# PCB.net
KiCad netlist of a schematic drawn in Altium Designer
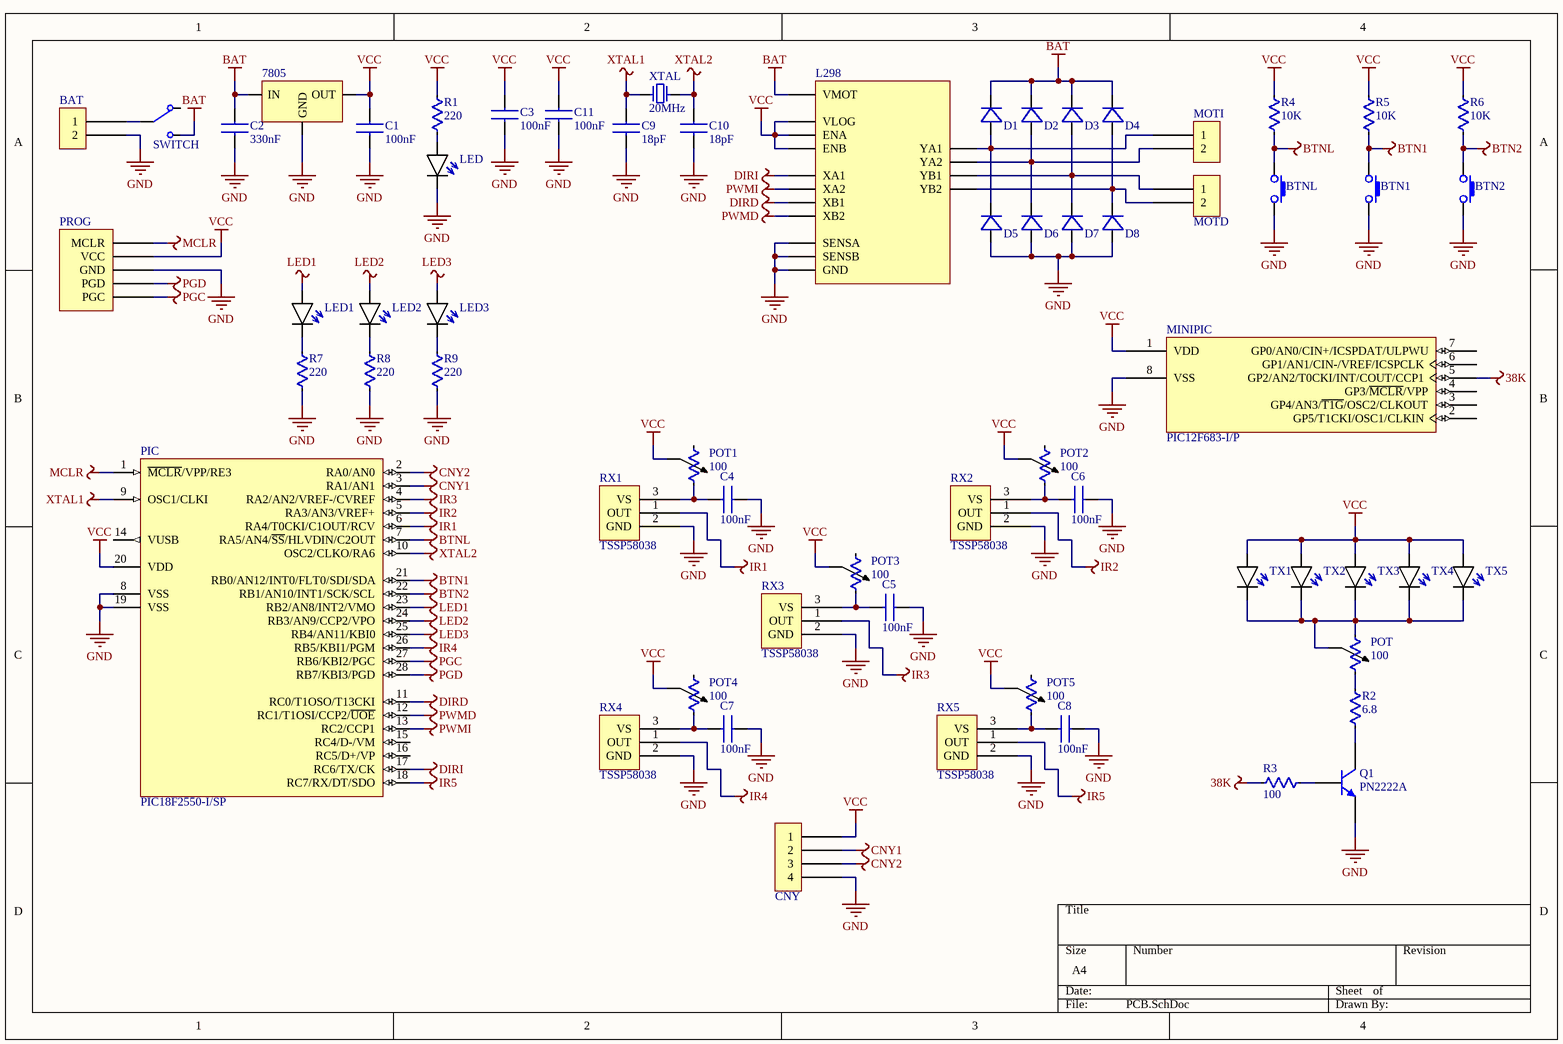
[diagram p0: PCB.SchDoc]

(export (version "E")
  (design (tool "Eeschema 10.0.6"))
  (components
    (comp (ref "7805")
      (value "LM78XX")
      (footprint "TO-220-FLAT")
      (libsource (lib "AltiumLibrary") (part "LM78XX"))
    )
    (comp (ref "BAT")
      (value "Header 1x2")
      (footprint "HEADER 1x2")
      (libsource (lib "AltiumLibrary") (part "Header 1x2"))
    )
    (comp (ref "BTN1")
      (value "BUTTON_SMALL_4PIN")
      (footprint "TACT_SWITCH-SMALL-4PIN")
      (libsource (lib "AltiumLibrary") (part "BUTTON_SMALL_4PIN"))
    )
    (comp (ref "BTN2")
      (value "BUTTON_SMALL_4PIN")
      (footprint "TACT_SWITCH-SMALL-4PIN")
      (libsource (lib "AltiumLibrary") (part "BUTTON_SMALL_4PIN"))
    )
    (comp (ref "BTNL")
      (value "BUTTON_SMALL_4PIN")
      (footprint "TACT_SWITCH-SMALL-4PIN")
      (libsource (lib "AltiumLibrary") (part "BUTTON_SMALL_4PIN"))
    )
    (comp (ref "C1")
      (value "100nF")
      (footprint "CAP-CER")
      (fields (field (name "Comment") "CAP-CER"))
      (libsource (lib "AltiumLibrary") (part "CAP-CER"))
    )
    (comp (ref "C2")
      (value "330nF")
      (footprint "CAP-CER")
      (fields (field (name "Comment") "CAP-CER"))
      (libsource (lib "AltiumLibrary") (part "CAP-CER"))
    )
    (comp (ref "C3")
      (value "100nF")
      (footprint "CAP-CER")
      (fields (field (name "Comment") "CAP-CER"))
      (libsource (lib "AltiumLibrary") (part "CAP-CER"))
    )
    (comp (ref "C4")
      (value "100nF")
      (footprint "CAP-CER")
      (fields (field (name "Comment") "CAP-CER"))
      (libsource (lib "AltiumLibrary") (part "CAP-CER"))
    )
    (comp (ref "C5")
      (value "100nF")
      (footprint "CAP-CER")
      (fields (field (name "Comment") "CAP-CER"))
      (libsource (lib "AltiumLibrary") (part "CAP-CER"))
    )
    (comp (ref "C6")
      (value "100nF")
      (footprint "CAP-CER")
      (fields (field (name "Comment") "CAP-CER"))
      (libsource (lib "AltiumLibrary") (part "CAP-CER"))
    )
    (comp (ref "C7")
      (value "100nF")
      (footprint "CAP-CER")
      (fields (field (name "Comment") "CAP-CER"))
      (libsource (lib "AltiumLibrary") (part "CAP-CER"))
    )
    (comp (ref "C8")
      (value "100nF")
      (footprint "CAP-CER")
      (fields (field (name "Comment") "CAP-CER"))
      (libsource (lib "AltiumLibrary") (part "CAP-CER"))
    )
    (comp (ref "C9")
      (value "18pF")
      (footprint "CAP-CER")
      (fields (field (name "Comment") "CAP-CER"))
      (libsource (lib "AltiumLibrary") (part "CAP-CER"))
    )
    (comp (ref "C10")
      (value "18pF")
      (footprint "CAP-CER")
      (fields (field (name "Comment") "CAP-CER"))
      (libsource (lib "AltiumLibrary") (part "CAP-CER"))
    )
    (comp (ref "C11")
      (value "100nF")
      (footprint "CAP-CER")
      (fields (field (name "Comment") "CAP-CER"))
      (libsource (lib "AltiumLibrary") (part "CAP-CER"))
    )
    (comp (ref "CNY")
      (value "Header 1x4")
      (footprint "Header 1x4")
      (libsource (lib "AltiumLibrary") (part "Header 1x4"))
    )
    (comp (ref "D1")
      (value "DIODE")
      (footprint "DO-41 RADIAL")
      (libsource (lib "AltiumLibrary") (part "DIODE"))
    )
    (comp (ref "D2")
      (value "DIODE")
      (footprint "DO-41 RADIAL")
      (libsource (lib "AltiumLibrary") (part "DIODE"))
    )
    (comp (ref "D3")
      (value "DIODE")
      (footprint "DO-41 RADIAL")
      (libsource (lib "AltiumLibrary") (part "DIODE"))
    )
    (comp (ref "D4")
      (value "DIODE")
      (footprint "DO-41 RADIAL")
      (libsource (lib "AltiumLibrary") (part "DIODE"))
    )
    (comp (ref "D5")
      (value "DIODE")
      (footprint "DO-41 RADIAL")
      (libsource (lib "AltiumLibrary") (part "DIODE"))
    )
    (comp (ref "D6")
      (value "DIODE")
      (footprint "DO-41 RADIAL")
      (libsource (lib "AltiumLibrary") (part "DIODE"))
    )
    (comp (ref "D7")
      (value "DIODE")
      (footprint "DO-41 RADIAL")
      (libsource (lib "AltiumLibrary") (part "DIODE"))
    )
    (comp (ref "D8")
      (value "DIODE")
      (footprint "DO-41 RADIAL")
      (libsource (lib "AltiumLibrary") (part "DIODE"))
    )
    (comp (ref "L298")
      (value "L298")
      (footprint "Multiwatt15")
      (libsource (lib "AltiumLibrary") (part "L298"))
    )
    (comp (ref "LED") (value "LED") (footprint "LED-3MM-RED") (libsource (lib "AltiumLibrary") (part "LED")))
    (comp (ref "LED1") (value "LED") (footprint "LED-3MM-RED") (libsource (lib "AltiumLibrary") (part "LED")))
    (comp (ref "LED2")
      (value "LED")
      (footprint "LED-3MM-YELLOW")
      (libsource (lib "AltiumLibrary") (part "LED"))
    )
    (comp (ref "LED3")
      (value "LED")
      (footprint "LED-3MM-GREEN")
      (libsource (lib "AltiumLibrary") (part "LED"))
    )
    (comp (ref "MINIPIC")
      (value "PIC12F683-I/P")
      (footprint "PDIP300-P8")
      (fields (field (name "PUBLISHER") "Altium Limited"))
      (libsource (lib "Microchip Microcontroller 8-Bit PIC12") (part "PIC12F683-I/P"))
    )
    (comp (ref "MOTD") (value "~") (footprint "HEADER 1x2") (libsource (lib "") (part "Header 1x2_1")))
    (comp (ref "MOTI") (value "~") (footprint "HEADER 1x2") (libsource (lib "") (part "Header 1x2_1")))
    (comp (ref "PIC")
      (value "PIC18F2550-I/SP")
      (footprint "SPDIP300-SP28")
      (fields (field (name "PUBLISHER") "Altium Limited"))
      (libsource (lib "Microchip Microcontroller 8-Bit PIC18") (part "PIC18F2550-I/SP"))
    )
    (comp (ref "POT")
      (value "100")
      (footprint "POT-10TURN")
      (fields (field (name "Comment") "POT"))
      (libsource (lib "AltiumLibrary") (part "POT"))
    )
    (comp (ref "POT1")
      (value "100")
      (footprint "POT-10TURN")
      (fields (field (name "Comment") "POT"))
      (libsource (lib "AltiumLibrary") (part "POT"))
    )
    (comp (ref "POT2")
      (value "100")
      (footprint "POT-10TURN")
      (fields (field (name "Comment") "POT"))
      (libsource (lib "AltiumLibrary") (part "POT"))
    )
    (comp (ref "POT3")
      (value "100")
      (footprint "POT-10TURN")
      (fields (field (name "Comment") "POT"))
      (libsource (lib "AltiumLibrary") (part "POT"))
    )
    (comp (ref "POT4")
      (value "100")
      (footprint "POT-10TURN")
      (fields (field (name "Comment") "POT"))
      (libsource (lib "AltiumLibrary") (part "POT"))
    )
    (comp (ref "POT5")
      (value "100")
      (footprint "POT-10TURN")
      (fields (field (name "Comment") "POT"))
      (libsource (lib "AltiumLibrary") (part "POT"))
    )
    (comp (ref "PROG")
      (value "~")
      (footprint "Header 1x5")
      (libsource (lib "AltiumLibrary") (part "Header Programmer"))
    )
    (comp (ref "Q1") (value "PN2222A") (footprint "TO-92") (libsource (lib "AltiumLibrary") (part "NPN")))
    (comp (ref "R1")
      (value "220")
      (footprint "RES-Axial-400mil")
      (fields (field (name "Comment") "RES"))
      (libsource (lib "") (part "RES_1"))
    )
    (comp (ref "R2")
      (value "6.8")
      (footprint "RES-Axial-400mil")
      (fields (field (name "Comment") "RES"))
      (libsource (lib "AltiumLibrary") (part "RES"))
    )
    (comp (ref "R3")
      (value "100")
      (footprint "RES-Axial-400mil")
      (fields (field (name "Comment") "RES"))
      (libsource (lib "") (part "RES_2"))
    )
    (comp (ref "R4")
      (value "10K")
      (footprint "RES-Axial-400mil")
      (fields (field (name "Comment") "RES"))
      (libsource (lib "") (part "RES_1"))
    )
    (comp (ref "R5")
      (value "10K")
      (footprint "RES-Axial-400mil")
      (fields (field (name "Comment") "RES"))
      (libsource (lib "") (part "RES_1"))
    )
    (comp (ref "R6")
      (value "10K")
      (footprint "RES-Axial-400mil")
      (fields (field (name "Comment") "RES"))
      (libsource (lib "") (part "RES_1"))
    )
    (comp (ref "R7")
      (value "220")
      (footprint "RES-RADIAL")
      (fields (field (name "Comment") "RES"))
      (libsource (lib "AltiumLibrary") (part "RES"))
    )
    (comp (ref "R8")
      (value "220")
      (footprint "RES-RADIAL")
      (fields (field (name "Comment") "RES"))
      (libsource (lib "AltiumLibrary") (part "RES"))
    )
    (comp (ref "R9")
      (value "220")
      (footprint "RES-RADIAL")
      (fields (field (name "Comment") "RES"))
      (libsource (lib "AltiumLibrary") (part "RES"))
    )
    (comp (ref "RX1")
      (value "TSSP58038")
      (footprint "TSSP58038")
      (libsource (lib "GlecerLib") (part "TSSP58038"))
    )
    (comp (ref "RX2")
      (value "TSSP58038")
      (footprint "TSSP58038")
      (libsource (lib "GlecerLib") (part "TSSP58038"))
    )
    (comp (ref "RX3")
      (value "TSSP58038")
      (footprint "TSSP58038")
      (libsource (lib "GlecerLib") (part "TSSP58038"))
    )
    (comp (ref "RX4")
      (value "TSSP58038")
      (footprint "TSSP58038")
      (libsource (lib "GlecerLib") (part "TSSP58038"))
    )
    (comp (ref "RX5")
      (value "TSSP58038")
      (footprint "TSSP58038")
      (libsource (lib "GlecerLib") (part "TSSP58038"))
    )
    (comp (ref "SWITCH")
      (value "SLIDE-SWITCH")
      (footprint "SWITCH")
      (libsource (lib "AltiumLibrary") (part "SLIDE-SWITCH"))
    )
    (comp (ref "TX1")
      (value "LED")
      (footprint "LED-3MM-YELLOW")
      (libsource (lib "AltiumLibrary") (part "LED"))
    )
    (comp (ref "TX2")
      (value "LED")
      (footprint "LED-3MM-YELLOW")
      (libsource (lib "AltiumLibrary") (part "LED"))
    )
    (comp (ref "TX3")
      (value "LED")
      (footprint "LED-3MM-YELLOW")
      (libsource (lib "AltiumLibrary") (part "LED"))
    )
    (comp (ref "TX4")
      (value "LED")
      (footprint "LED-3MM-YELLOW")
      (libsource (lib "AltiumLibrary") (part "LED"))
    )
    (comp (ref "TX5")
      (value "LED")
      (footprint "LED-3MM-YELLOW")
      (libsource (lib "AltiumLibrary") (part "LED"))
    )
    (comp (ref "XTAL")
      (value "XTAL")
      (footprint "CRYSTAL-TH")
      (fields (field (name "FREQUENCY") "20MHz"))
      (libsource (lib "AltiumLibrary") (part "XTAL"))
    )
  )
  (nets
    (net (code "1") (name "38K") (class "Default")
      (node (ref "MINIPIC") (pin "5") (pinfunction "GP2/AN2/T0CKI/INT/COUT/CCP1_5") (pintype "bidirectional"))
      (node (ref "R3") (pin "1") (pintype "passive"))
    )
    (net (code "2") (name "BAT") (class "Default")
      (node (ref "7805") (pin "1") (pinfunction "IN_1") (pintype "power_in"))
      (node (ref "C2") (pin "1") (pintype "passive"))
      (node (ref "D1") (pin "K") (pintype "passive"))
      (node (ref "D2") (pin "K") (pintype "passive"))
      (node (ref "D3") (pin "K") (pintype "passive"))
      (node (ref "D4") (pin "K") (pintype "passive"))
      (node (ref "L298") (pin "4") (pinfunction "VMOT_4") (pintype "passive"))
      (node (ref "SWITCH") (pin "3") (pintype "power_in"))
    )
    (net (code "3") (name "BTN1") (class "Default")
      (node (ref "BTN1") (pin "1") (pintype "passive"))
      (node (ref "PIC") (pin "21") (pinfunction "RB0/AN12/INT0/FLT0/SDI/SDA_21") (pintype "bidirectional"))
      (node (ref "R5") (pin "1") (pintype "passive"))
    )
    (net (code "4") (name "BTN2") (class "Default")
      (node (ref "BTN2") (pin "1") (pintype "passive"))
      (node (ref "PIC") (pin "22") (pinfunction "RB1/AN10/INT1/SCK/SCL_22") (pintype "bidirectional"))
      (node (ref "R6") (pin "1") (pintype "passive"))
    )
    (net (code "5") (name "BTNL") (class "Default")
      (node (ref "BTNL") (pin "1") (pintype "passive"))
      (node (ref "PIC") (pin "7") (pinfunction "RA5/AN4/~{SS}/HLVDIN/C2OUT_7") (pintype "bidirectional"))
      (node (ref "R4") (pin "1") (pintype "passive"))
    )
    (net (code "6") (name "CNY1") (class "Default")
      (node (ref "CNY") (pin "2") (pinfunction "2_2") (pintype "passive"))
      (node (ref "PIC") (pin "3") (pinfunction "RA1/AN1_3") (pintype "bidirectional"))
    )
    (net (code "7") (name "CNY2") (class "Default")
      (node (ref "CNY") (pin "3") (pinfunction "3_3") (pintype "passive"))
      (node (ref "PIC") (pin "2") (pinfunction "RA0/AN0_2") (pintype "bidirectional"))
    )
    (net (code "8") (name "DIRD") (class "Default")
      (node (ref "L298") (pin "12") (pinfunction "XB1_12") (pintype "passive"))
      (node (ref "PIC") (pin "11") (pinfunction "RC0/T1OSO/T13CKI_11") (pintype "bidirectional"))
    )
    (net (code "9") (name "DIRI") (class "Default")
      (node (ref "L298") (pin "5") (pinfunction "XA1_5") (pintype "passive"))
      (node (ref "PIC") (pin "17") (pinfunction "RC6/TX/CK_17") (pintype "bidirectional"))
    )
    (net (code "10") (name "GND") (class "Default")
      (node (ref "7805") (pin "2") (pinfunction "GND_2") (pintype "power_in"))
      (node (ref "BAT") (pin "2") (pinfunction "2_2") (pintype "passive"))
      (node (ref "BTN1") (pin "2") (pintype "passive"))
      (node (ref "BTN2") (pin "2") (pintype "passive"))
      (node (ref "BTNL") (pin "2") (pintype "passive"))
      (node (ref "C1") (pin "2") (pintype "passive"))
      (node (ref "C10") (pin "1") (pintype "passive"))
      (node (ref "C11") (pin "1") (pintype "passive"))
      (node (ref "C2") (pin "2") (pintype "passive"))
      (node (ref "C3") (pin "1") (pintype "passive"))
      (node (ref "C4") (pin "2") (pintype "passive"))
      (node (ref "C5") (pin "2") (pintype "passive"))
      (node (ref "C6") (pin "2") (pintype "passive"))
      (node (ref "C7") (pin "2") (pintype "passive"))
      (node (ref "C8") (pin "2") (pintype "passive"))
      (node (ref "C9") (pin "1") (pintype "passive"))
      (node (ref "CNY") (pin "4") (pinfunction "4_4") (pintype "passive"))
      (node (ref "D5") (pin "A") (pintype "passive"))
      (node (ref "D6") (pin "A") (pintype "passive"))
      (node (ref "D7") (pin "A") (pintype "passive"))
      (node (ref "D8") (pin "A") (pintype "passive"))
      (node (ref "L298") (pin "1") (pinfunction "SENSA_1") (pintype "passive"))
      (node (ref "L298") (pin "15") (pinfunction "SENSB_15") (pintype "passive"))
      (node (ref "L298") (pin "8") (pinfunction "GND_8") (pintype "passive"))
      (node (ref "LED") (pin "K") (pintype "passive"))
      (node (ref "MINIPIC") (pin "8") (pinfunction "VSS_8") (pintype "power_in"))
      (node (ref "PIC") (pin "19") (pinfunction "VSS_19") (pintype "power_in"))
      (node (ref "PIC") (pin "8") (pinfunction "VSS_8") (pintype "power_in"))
      (node (ref "PROG") (pin "3") (pinfunction "GND_3") (pintype "power_in"))
      (node (ref "Q1") (pin "E") (pinfunction "E_E") (pintype "passive"))
      (node (ref "R7") (pin "2") (pintype "passive"))
      (node (ref "R8") (pin "2") (pintype "passive"))
      (node (ref "R9") (pin "2") (pintype "passive"))
      (node (ref "RX1") (pin "2") (pinfunction "GND_2") (pintype "power_in"))
      (node (ref "RX2") (pin "2") (pinfunction "GND_2") (pintype "power_in"))
      (node (ref "RX3") (pin "2") (pinfunction "GND_2") (pintype "power_in"))
      (node (ref "RX4") (pin "2") (pinfunction "GND_2") (pintype "power_in"))
      (node (ref "RX5") (pin "2") (pinfunction "GND_2") (pintype "power_in"))
    )
    (net (code "11") (name "IR1") (class "Default")
      (node (ref "PIC") (pin "6") (pinfunction "RA4/T0CKI/C1OUT/RCV_6") (pintype "bidirectional"))
      (node (ref "RX1") (pin "1") (pinfunction "OUT_1") (pintype "power_in"))
    )
    (net (code "12") (name "IR2") (class "Default")
      (node (ref "PIC") (pin "5") (pinfunction "RA3/AN3/VREF+_5") (pintype "bidirectional"))
      (node (ref "RX2") (pin "1") (pinfunction "OUT_1") (pintype "power_in"))
    )
    (net (code "13") (name "IR3") (class "Default")
      (node (ref "PIC") (pin "4") (pinfunction "RA2/AN2/VREF-/CVREF_4") (pintype "bidirectional"))
      (node (ref "RX3") (pin "1") (pinfunction "OUT_1") (pintype "power_in"))
    )
    (net (code "14") (name "IR4") (class "Default")
      (node (ref "PIC") (pin "26") (pinfunction "RB5/KBI1/PGM_26") (pintype "bidirectional"))
      (node (ref "RX4") (pin "1") (pinfunction "OUT_1") (pintype "power_in"))
    )
    (net (code "15") (name "IR5") (class "Default")
      (node (ref "PIC") (pin "18") (pinfunction "RC7/RX/DT/SDO_18") (pintype "bidirectional"))
      (node (ref "RX5") (pin "1") (pinfunction "OUT_1") (pintype "power_in"))
    )
    (net (code "16") (name "LED1") (class "Default")
      (node (ref "LED1") (pin "A") (pintype "passive"))
      (node (ref "PIC") (pin "23") (pinfunction "RB2/AN8/INT2/VMO_23") (pintype "bidirectional"))
    )
    (net (code "17") (name "LED2") (class "Default")
      (node (ref "LED2") (pin "A") (pintype "passive"))
      (node (ref "PIC") (pin "24") (pinfunction "RB3/AN9/CCP2/VPO_24") (pintype "bidirectional"))
    )
    (net (code "18") (name "LED3") (class "Default")
      (node (ref "LED3") (pin "A") (pintype "passive"))
      (node (ref "PIC") (pin "25") (pinfunction "RB4/AN11/KBI0_25") (pintype "bidirectional"))
    )
    (net (code "19") (name "MCLR") (class "Default")
      (node (ref "PIC") (pin "1") (pinfunction "~{MCLR}/VPP/RE3_1") (pintype "input"))
      (node (ref "PROG") (pin "1") (pinfunction "MCLR_1") (pintype "passive"))
    )
    (net (code "20") (name "Net-(BAT-Pad1)") (class "Default")
      (node (ref "BAT") (pin "1") (pinfunction "1_1") (pintype "passive"))
      (node (ref "SWITCH") (pin "2") (pintype "power_in"))
    )
    (net (code "21") (name "Net-(L298-YA1)") (class "Default")
      (node (ref "D1") (pin "A") (pintype "passive"))
      (node (ref "D5") (pin "K") (pintype "passive"))
      (node (ref "L298") (pin "2") (pinfunction "YA1_2") (pintype "passive"))
      (node (ref "MOTI") (pin "1") (pinfunction "1_1") (pintype "passive"))
    )
    (net (code "22") (name "Net-(L298-YA2)") (class "Default")
      (node (ref "D2") (pin "A") (pintype "passive"))
      (node (ref "D6") (pin "K") (pintype "passive"))
      (node (ref "L298") (pin "3") (pinfunction "YA2_3") (pintype "passive"))
      (node (ref "MOTI") (pin "2") (pinfunction "2_2") (pintype "passive"))
    )
    (net (code "23") (name "Net-(L298-YB1)") (class "Default")
      (node (ref "D3") (pin "A") (pintype "passive"))
      (node (ref "D7") (pin "K") (pintype "passive"))
      (node (ref "L298") (pin "13") (pinfunction "YB1_13") (pintype "passive"))
      (node (ref "MOTD") (pin "1") (pinfunction "1_1") (pintype "passive"))
    )
    (net (code "24") (name "Net-(L298-YB2)") (class "Default")
      (node (ref "D4") (pin "A") (pintype "passive"))
      (node (ref "D8") (pin "K") (pintype "passive"))
      (node (ref "L298") (pin "14") (pinfunction "YB2_14") (pintype "passive"))
      (node (ref "MOTD") (pin "2") (pinfunction "2_2") (pintype "passive"))
    )
    (net (code "25") (name "Net-(LED-PadA)") (class "Default")
      (node (ref "LED") (pin "A") (pintype "passive"))
      (node (ref "R1") (pin "1") (pintype "passive"))
    )
    (net (code "26") (name "Net-(LED1-PadK)") (class "Default")
      (node (ref "LED1") (pin "K") (pintype "passive"))
      (node (ref "R7") (pin "1") (pintype "passive"))
    )
    (net (code "27") (name "Net-(LED2-PadK)") (class "Default")
      (node (ref "LED2") (pin "K") (pintype "passive"))
      (node (ref "R8") (pin "1") (pintype "passive"))
    )
    (net (code "28") (name "Net-(LED3-PadK)") (class "Default")
      (node (ref "LED3") (pin "K") (pintype "passive"))
      (node (ref "R9") (pin "1") (pintype "passive"))
    )
    (net (code "29") (name "Net-(POT-Pad1)") (class "Default")
      (node (ref "POT") (pin "1") (pintype "passive"))
      (node (ref "R2") (pin "1") (pintype "passive"))
    )
    (net (code "30") (name "Net-(POT-Pad2)") (class "Default")
      (node (ref "POT") (pin "2") (pintype "passive"))
      (node (ref "POT") (pin "3") (pintype "passive"))
      (node (ref "TX1") (pin "K") (pintype "passive"))
      (node (ref "TX2") (pin "K") (pintype "passive"))
      (node (ref "TX3") (pin "K") (pintype "passive"))
      (node (ref "TX4") (pin "K") (pintype "passive"))
      (node (ref "TX5") (pin "K") (pintype "passive"))
    )
    (net (code "31") (name "Net-(Q1-PadB)") (class "Default")
      (node (ref "Q1") (pin "B") (pinfunction "B_B") (pintype "passive"))
      (node (ref "R3") (pin "2") (pintype "passive"))
    )
    (net (code "32") (name "Net-(Q1-PadC)") (class "Default")
      (node (ref "Q1") (pin "C") (pinfunction "C_C") (pintype "passive"))
      (node (ref "R2") (pin "2") (pintype "passive"))
    )
    (net (code "33") (name "Net-(RX1-VS)") (class "Default")
      (node (ref "C4") (pin "1") (pintype "passive"))
      (node (ref "POT1") (pin "1") (pintype "passive"))
      (node (ref "RX1") (pin "3") (pinfunction "VS_3") (pintype "power_in"))
    )
    (net (code "34") (name "Net-(RX2-VS)") (class "Default")
      (node (ref "C6") (pin "1") (pintype "passive"))
      (node (ref "POT2") (pin "1") (pintype "passive"))
      (node (ref "RX2") (pin "3") (pinfunction "VS_3") (pintype "power_in"))
    )
    (net (code "35") (name "Net-(RX3-VS)") (class "Default")
      (node (ref "C5") (pin "1") (pintype "passive"))
      (node (ref "POT3") (pin "1") (pintype "passive"))
      (node (ref "RX3") (pin "3") (pinfunction "VS_3") (pintype "power_in"))
    )
    (net (code "36") (name "Net-(RX4-VS)") (class "Default")
      (node (ref "C7") (pin "1") (pintype "passive"))
      (node (ref "POT4") (pin "1") (pintype "passive"))
      (node (ref "RX4") (pin "3") (pinfunction "VS_3") (pintype "power_in"))
    )
    (net (code "37") (name "Net-(RX5-VS)") (class "Default")
      (node (ref "C8") (pin "1") (pintype "passive"))
      (node (ref "POT5") (pin "1") (pintype "passive"))
      (node (ref "RX5") (pin "3") (pinfunction "VS_3") (pintype "power_in"))
    )
    (net (code "38") (name "PGC") (class "Default")
      (node (ref "PIC") (pin "27") (pinfunction "RB6/KBI2/PGC_27") (pintype "bidirectional"))
      (node (ref "PROG") (pin "5") (pinfunction "PGC_5") (pintype "passive"))
    )
    (net (code "39") (name "PGD") (class "Default")
      (node (ref "PIC") (pin "28") (pinfunction "RB7/KBI3/PGD_28") (pintype "bidirectional"))
      (node (ref "PROG") (pin "4") (pinfunction "PGD_4") (pintype "passive"))
    )
    (net (code "40") (name "PWMD") (class "Default")
      (node (ref "L298") (pin "10") (pinfunction "XB2_10") (pintype "passive"))
      (node (ref "PIC") (pin "12") (pinfunction "RC1/T1OSI/CCP2/~{UOE}_12") (pintype "bidirectional"))
    )
    (net (code "41") (name "PWMI") (class "Default")
      (node (ref "L298") (pin "7") (pinfunction "XA2_7") (pintype "passive"))
      (node (ref "PIC") (pin "13") (pinfunction "RC2/CCP1_13") (pintype "bidirectional"))
    )
    (net (code "42") (name "VCC") (class "Default")
      (node (ref "7805") (pin "3") (pinfunction "OUT_3") (pintype "power_in"))
      (node (ref "C1") (pin "1") (pintype "passive"))
      (node (ref "C11") (pin "2") (pintype "passive"))
      (node (ref "C3") (pin "2") (pintype "passive"))
      (node (ref "CNY") (pin "1") (pinfunction "1_1") (pintype "passive"))
      (node (ref "L298") (pin "11") (pinfunction "ENB_11") (pintype "passive"))
      (node (ref "L298") (pin "6") (pinfunction "ENA_6") (pintype "passive"))
      (node (ref "L298") (pin "9") (pinfunction "VLOG_9") (pintype "passive"))
      (node (ref "MINIPIC") (pin "1") (pinfunction "VDD_1") (pintype "power_in"))
      (node (ref "PIC") (pin "20") (pinfunction "VDD_20") (pintype "power_in"))
      (node (ref "POT1") (pin "2") (pintype "passive"))
      (node (ref "POT2") (pin "2") (pintype "passive"))
      (node (ref "POT3") (pin "2") (pintype "passive"))
      (node (ref "POT4") (pin "2") (pintype "passive"))
      (node (ref "POT5") (pin "2") (pintype "passive"))
      (node (ref "PROG") (pin "2") (pinfunction "VCC_2") (pintype "power_in"))
      (node (ref "R1") (pin "2") (pintype "passive"))
      (node (ref "R4") (pin "2") (pintype "passive"))
      (node (ref "R5") (pin "2") (pintype "passive"))
      (node (ref "R6") (pin "2") (pintype "passive"))
      (node (ref "TX1") (pin "A") (pintype "passive"))
      (node (ref "TX2") (pin "A") (pintype "passive"))
      (node (ref "TX3") (pin "A") (pintype "passive"))
      (node (ref "TX4") (pin "A") (pintype "passive"))
      (node (ref "TX5") (pin "A") (pintype "passive"))
    )
    (net (code "43") (name "XTAL1") (class "Default")
      (node (ref "C9") (pin "2") (pintype "passive"))
      (node (ref "PIC") (pin "9") (pinfunction "OSC1/CLKI_9") (pintype "input"))
      (node (ref "XTAL") (pin "1") (pintype "passive"))
    )
    (net (code "44") (name "XTAL2") (class "Default")
      (node (ref "C10") (pin "2") (pintype "passive"))
      (node (ref "PIC") (pin "10") (pinfunction "OSC2/CLKO/RA6_10") (pintype "bidirectional"))
      (node (ref "XTAL") (pin "2") (pintype "passive"))
    )
    (net (code "45") (name "unconnected-(MINIPIC-GP0{slash}AN0{slash}CIN+{slash}ICSPDAT{slash}ULPWU-Pad7)") (class "Default")
      (node (ref "MINIPIC") (pin "7") (pinfunction "GP0/AN0/CIN+/ICSPDAT/ULPWU_7") (pintype "bidirectional"))
    )
    (net (code "46") (name "unconnected-(MINIPIC-GP1{slash}AN1{slash}CIN-{slash}VREF{slash}ICSPCLK-Pad6)") (class "Default")
      (node (ref "MINIPIC") (pin "6") (pinfunction "GP1/AN1/CIN-/VREF/ICSPCLK_6") (pintype "bidirectional"))
    )
    (net (code "47") (name "unconnected-(MINIPIC-GP3{slash}~{MCLR}{slash}VPP-Pad4)") (class "Default")
      (node (ref "MINIPIC") (pin "4") (pinfunction "GP3/~{MCLR}/VPP_4") (pintype "bidirectional"))
    )
    (net (code "48") (name "unconnected-(MINIPIC-GP4{slash}AN3{slash}~{T1G}{slash}OSC2{slash}CLKOUT-Pad3)") (class "Default")
      (node (ref "MINIPIC") (pin "3") (pinfunction "GP4/AN3/~{T1G}/OSC2/CLKOUT_3") (pintype "bidirectional"))
    )
    (net (code "49") (name "unconnected-(MINIPIC-GP5{slash}T1CKI{slash}OSC1{slash}CLKIN-Pad2)") (class "Default")
      (node (ref "MINIPIC") (pin "2") (pinfunction "GP5/T1CKI/OSC1/CLKIN_2") (pintype "bidirectional"))
    )
    (net (code "50") (name "unconnected-(PIC-RC4{slash}D-{slash}VM-Pad15)") (class "Default")
      (node (ref "PIC") (pin "15") (pinfunction "RC4/D-/VM_15") (pintype "bidirectional"))
    )
    (net (code "51") (name "unconnected-(PIC-RC5{slash}D+{slash}VP-Pad16)") (class "Default")
      (node (ref "PIC") (pin "16") (pinfunction "RC5/D+/VP_16") (pintype "bidirectional"))
    )
    (net (code "52") (name "unconnected-(PIC-VUSB-Pad14)") (class "Default")
      (node (ref "PIC") (pin "14") (pinfunction "VUSB_14") (pintype "output"))
    )
    (net (code "53") (name "unconnected-(POT1-Pad3)") (class "Default")
      (node (ref "POT1") (pin "3") (pintype "passive"))
    )
    (net (code "54") (name "unconnected-(POT2-Pad3)") (class "Default")
      (node (ref "POT2") (pin "3") (pintype "passive"))
    )
    (net (code "55") (name "unconnected-(POT3-Pad3)") (class "Default")
      (node (ref "POT3") (pin "3") (pintype "passive"))
    )
    (net (code "56") (name "unconnected-(POT4-Pad3)") (class "Default")
      (node (ref "POT4") (pin "3") (pintype "passive"))
    )
    (net (code "57") (name "unconnected-(POT5-Pad3)") (class "Default")
      (node (ref "POT5") (pin "3") (pintype "passive"))
    )
    (net (code "58") (name "unconnected-(SWITCH-Pad1)") (class "Default")
      (node (ref "SWITCH") (pin "1") (pintype "power_in"))
    )
  )
)
